# ajuste-sensor-temperatura2.net
KiCad netlist of a schematic drawn in EAGLE
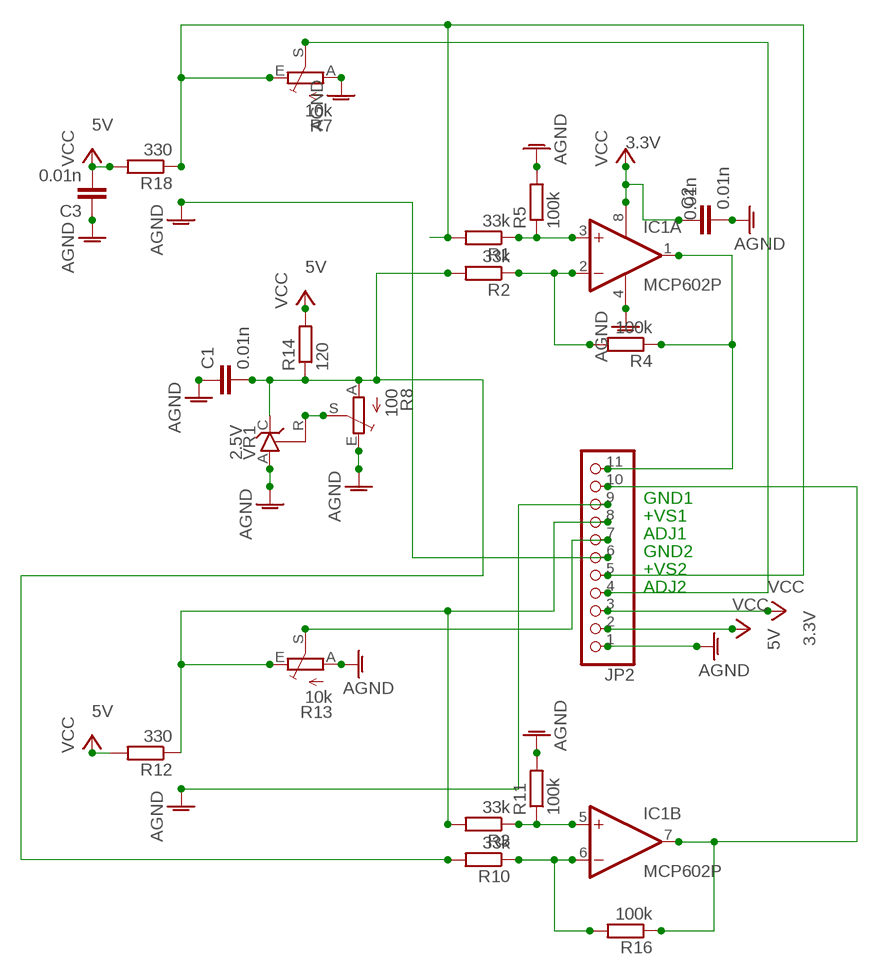
[diagram p0: schematic, sheet 1]

(export (version "E")
  (design (tool "Eeschema 10.0.6"))
  (components
    (comp (ref "C1")
      (value "0.01n")
      (footprint "eagle-import:C7.5B3")
      (libsource (lib "eagle-import") (part "C7.5/3"))
    )
    (comp (ref "C2")
      (value "0.01n")
      (footprint "eagle-import:C7.5B3")
      (fields (field (name "C1") "0.01n"))
      (libsource (lib "eagle-import") (part "C7.5/3"))
    )
    (comp (ref "C3")
      (value "0.01n")
      (footprint "eagle-import:C7.5B3")
      (libsource (lib "eagle-import") (part "C7.5/3"))
    )
    (comp (ref "IC1")
      (value "MCP602P")
      (footprint "eagle-import:DIL08")
      (libsource (lib "eagle-import") (part "MCP602P"))
    )
    (comp (ref "JP2")
      (value "PINHD-1X11")
      (footprint "eagle-import:1X11")
      (libsource (lib "eagle-import") (part "PINHD-1X11"))
    )
    (comp (ref "R1")
      (value "33k")
      (footprint "eagle-import:0204_7")
      (libsource (lib "eagle-import") (part "R-EU_0204/7"))
    )
    (comp (ref "R2")
      (value "33k")
      (footprint "eagle-import:0204_7")
      (libsource (lib "eagle-import") (part "R-EU_0204/7"))
    )
    (comp (ref "R3")
      (value "33k")
      (footprint "eagle-import:0204_7")
      (libsource (lib "eagle-import") (part "R-EU_0204/7"))
    )
    (comp (ref "R4")
      (value "100k")
      (footprint "eagle-import:0204_7")
      (libsource (lib "eagle-import") (part "R-EU_0204/7"))
    )
    (comp (ref "R5")
      (value "100k")
      (footprint "eagle-import:0204_7")
      (libsource (lib "eagle-import") (part "R-EU_0204/7"))
    )
    (comp (ref "R7")
      (value "10k")
      (footprint "eagle-import:CA9V")
      (libsource (lib "eagle-import") (part "TRIM_EU-CA9V"))
    )
    (comp (ref "R8")
      (value "100")
      (footprint "eagle-import:CA9V")
      (libsource (lib "eagle-import") (part "TRIM_EU-CA9V"))
    )
    (comp (ref "R10")
      (value "33k")
      (footprint "eagle-import:0204_7")
      (libsource (lib "eagle-import") (part "R-EU_0204/7"))
    )
    (comp (ref "R11")
      (value "100k")
      (footprint "eagle-import:0204_7")
      (libsource (lib "eagle-import") (part "R-EU_0204/7"))
    )
    (comp (ref "R12")
      (value "330")
      (footprint "eagle-import:0204_7")
      (libsource (lib "eagle-import") (part "R-EU_0204/7"))
    )
    (comp (ref "R13")
      (value "10k")
      (footprint "eagle-import:CA9V")
      (libsource (lib "eagle-import") (part "TRIM_EU-CA9V"))
    )
    (comp (ref "R14")
      (value "120")
      (footprint "eagle-import:0204_7")
      (libsource (lib "eagle-import") (part "R-EU_0204/7"))
    )
    (comp (ref "R16")
      (value "100k")
      (footprint "eagle-import:0204_7")
      (libsource (lib "eagle-import") (part "R-EU_0204/7"))
    )
    (comp (ref "R18")
      (value "330")
      (footprint "eagle-import:0204_7")
      (libsource (lib "eagle-import") (part "R-EU_0204/7"))
    )
    (comp (ref "VR1")
      (value "2.5V")
      (footprint "eagle-import:TO92-CLP")
      (libsource (lib "eagle-import") (part "TL431CLP"))
    )
  )
  (nets
    (net (code "1") (name "AGND") (class "Default")
      (node (ref "C1") (pin "1") (pinfunction "1_1") (pintype "passive"))
      (node (ref "C2") (pin "2") (pinfunction "2_2") (pintype "passive"))
      (node (ref "C3") (pin "1") (pinfunction "1_1") (pintype "passive"))
      (node (ref "IC1") (pin "4") (pinfunction "V-_4") (pintype "power_in"))
      (node (ref "JP2") (pin "1") (pinfunction "1_1") (pintype "passive"))
      (node (ref "JP2") (pin "6") (pinfunction "6_6") (pintype "passive"))
      (node (ref "JP2") (pin "9") (pinfunction "9_9") (pintype "passive"))
      (node (ref "R11") (pin "2") (pinfunction "2_2") (pintype "passive"))
      (node (ref "R13") (pin "A") (pinfunction "A_A") (pintype "passive"))
      (node (ref "R5") (pin "2") (pinfunction "2_2") (pintype "passive"))
      (node (ref "R7") (pin "A") (pinfunction "A_A") (pintype "passive"))
      (node (ref "R8") (pin "E") (pinfunction "E_E") (pintype "passive"))
      (node (ref "VR1") (pin "A") (pinfunction "A_A") (pintype "passive"))
    )
    (net (code "2") (name "Net-(C1-Pad2)") (class "Default")
      (node (ref "C1") (pin "2") (pinfunction "2_2") (pintype "passive"))
      (node (ref "R10") (pin "2") (pinfunction "2_2") (pintype "passive"))
      (node (ref "R14") (pin "1") (pinfunction "1_1") (pintype "passive"))
      (node (ref "R2") (pin "2") (pinfunction "2_2") (pintype "passive"))
      (node (ref "R8") (pin "A") (pinfunction "A_A") (pintype "passive"))
      (node (ref "VR1") (pin "C") (pinfunction "C_C") (pintype "passive"))
    )
    (net (code "3") (name "Net-(IC1A-+IN)") (class "Default")
      (node (ref "IC1") (pin "3") (pinfunction "+IN_3") (pintype "input"))
      (node (ref "R1") (pin "1") (pinfunction "1_1") (pintype "passive"))
      (node (ref "R5") (pin "1") (pinfunction "1_1") (pintype "passive"))
    )
    (net (code "4") (name "Net-(IC1A--IN)") (class "Default")
      (node (ref "IC1") (pin "2") (pinfunction "-IN_2") (pintype "input"))
      (node (ref "R2") (pin "1") (pinfunction "1_1") (pintype "passive"))
      (node (ref "R4") (pin "2") (pinfunction "2_2") (pintype "passive"))
    )
    (net (code "5") (name "Net-(IC1A-OUT)") (class "Default")
      (node (ref "IC1") (pin "1") (pinfunction "OUT_1") (pintype "output"))
      (node (ref "JP2") (pin "11") (pinfunction "11_11") (pintype "passive"))
      (node (ref "R4") (pin "1") (pinfunction "1_1") (pintype "passive"))
    )
    (net (code "6") (name "Net-(IC1B-+IN)") (class "Default")
      (node (ref "IC1") (pin "5") (pinfunction "+IN_5") (pintype "input"))
      (node (ref "R11") (pin "1") (pinfunction "1_1") (pintype "passive"))
      (node (ref "R3") (pin "1") (pinfunction "1_1") (pintype "passive"))
    )
    (net (code "7") (name "Net-(IC1B--IN)") (class "Default")
      (node (ref "IC1") (pin "6") (pinfunction "-IN_6") (pintype "input"))
      (node (ref "R10") (pin "1") (pinfunction "1_1") (pintype "passive"))
      (node (ref "R16") (pin "2") (pinfunction "2_2") (pintype "passive"))
    )
    (net (code "8") (name "Net-(IC1B-OUT)") (class "Default")
      (node (ref "IC1") (pin "7") (pinfunction "OUT_7") (pintype "output"))
      (node (ref "JP2") (pin "10") (pinfunction "10_10") (pintype "passive"))
      (node (ref "R16") (pin "1") (pinfunction "1_1") (pintype "passive"))
    )
    (net (code "9") (name "Net-(JP2-Pad4)") (class "Default")
      (node (ref "JP2") (pin "4") (pinfunction "4_4") (pintype "passive"))
      (node (ref "R7") (pin "S") (pinfunction "S_S") (pintype "passive"))
    )
    (net (code "10") (name "Net-(JP2-Pad5)") (class "Default")
      (node (ref "JP2") (pin "5") (pinfunction "5_5") (pintype "passive"))
      (node (ref "R1") (pin "2") (pinfunction "2_2") (pintype "passive"))
      (node (ref "R18") (pin "1") (pinfunction "1_1") (pintype "passive"))
      (node (ref "R7") (pin "E") (pinfunction "E_E") (pintype "passive"))
    )
    (net (code "11") (name "Net-(JP2-Pad7)") (class "Default")
      (node (ref "JP2") (pin "7") (pinfunction "7_7") (pintype "passive"))
      (node (ref "R13") (pin "S") (pinfunction "S_S") (pintype "passive"))
    )
    (net (code "12") (name "Net-(JP2-Pad8)") (class "Default")
      (node (ref "JP2") (pin "8") (pinfunction "8_8") (pintype "passive"))
      (node (ref "R12") (pin "1") (pinfunction "1_1") (pintype "passive"))
      (node (ref "R13") (pin "E") (pinfunction "E_E") (pintype "passive"))
      (node (ref "R3") (pin "2") (pinfunction "2_2") (pintype "passive"))
    )
    (net (code "13") (name "Net-(R8-PadS)") (class "Default")
      (node (ref "R8") (pin "S") (pinfunction "S_S") (pintype "passive"))
      (node (ref "VR1") (pin "R") (pinfunction "R_R") (pintype "passive"))
    )
    (net (code "14") (name "VCC") (class "Default")
      (node (ref "C2") (pin "1") (pinfunction "1_1") (pintype "passive"))
      (node (ref "C3") (pin "2") (pinfunction "2_2") (pintype "passive"))
      (node (ref "IC1") (pin "8") (pinfunction "V+_8") (pintype "power_in"))
      (node (ref "JP2") (pin "2") (pinfunction "2_2") (pintype "passive"))
      (node (ref "JP2") (pin "3") (pinfunction "3_3") (pintype "passive"))
      (node (ref "R12") (pin "2") (pinfunction "2_2") (pintype "passive"))
      (node (ref "R14") (pin "2") (pinfunction "2_2") (pintype "passive"))
      (node (ref "R18") (pin "2") (pinfunction "2_2") (pintype "passive"))
    )
  )
)
